# 04_Power.net
KiCad netlist of a schematic drawn in Altium Designer
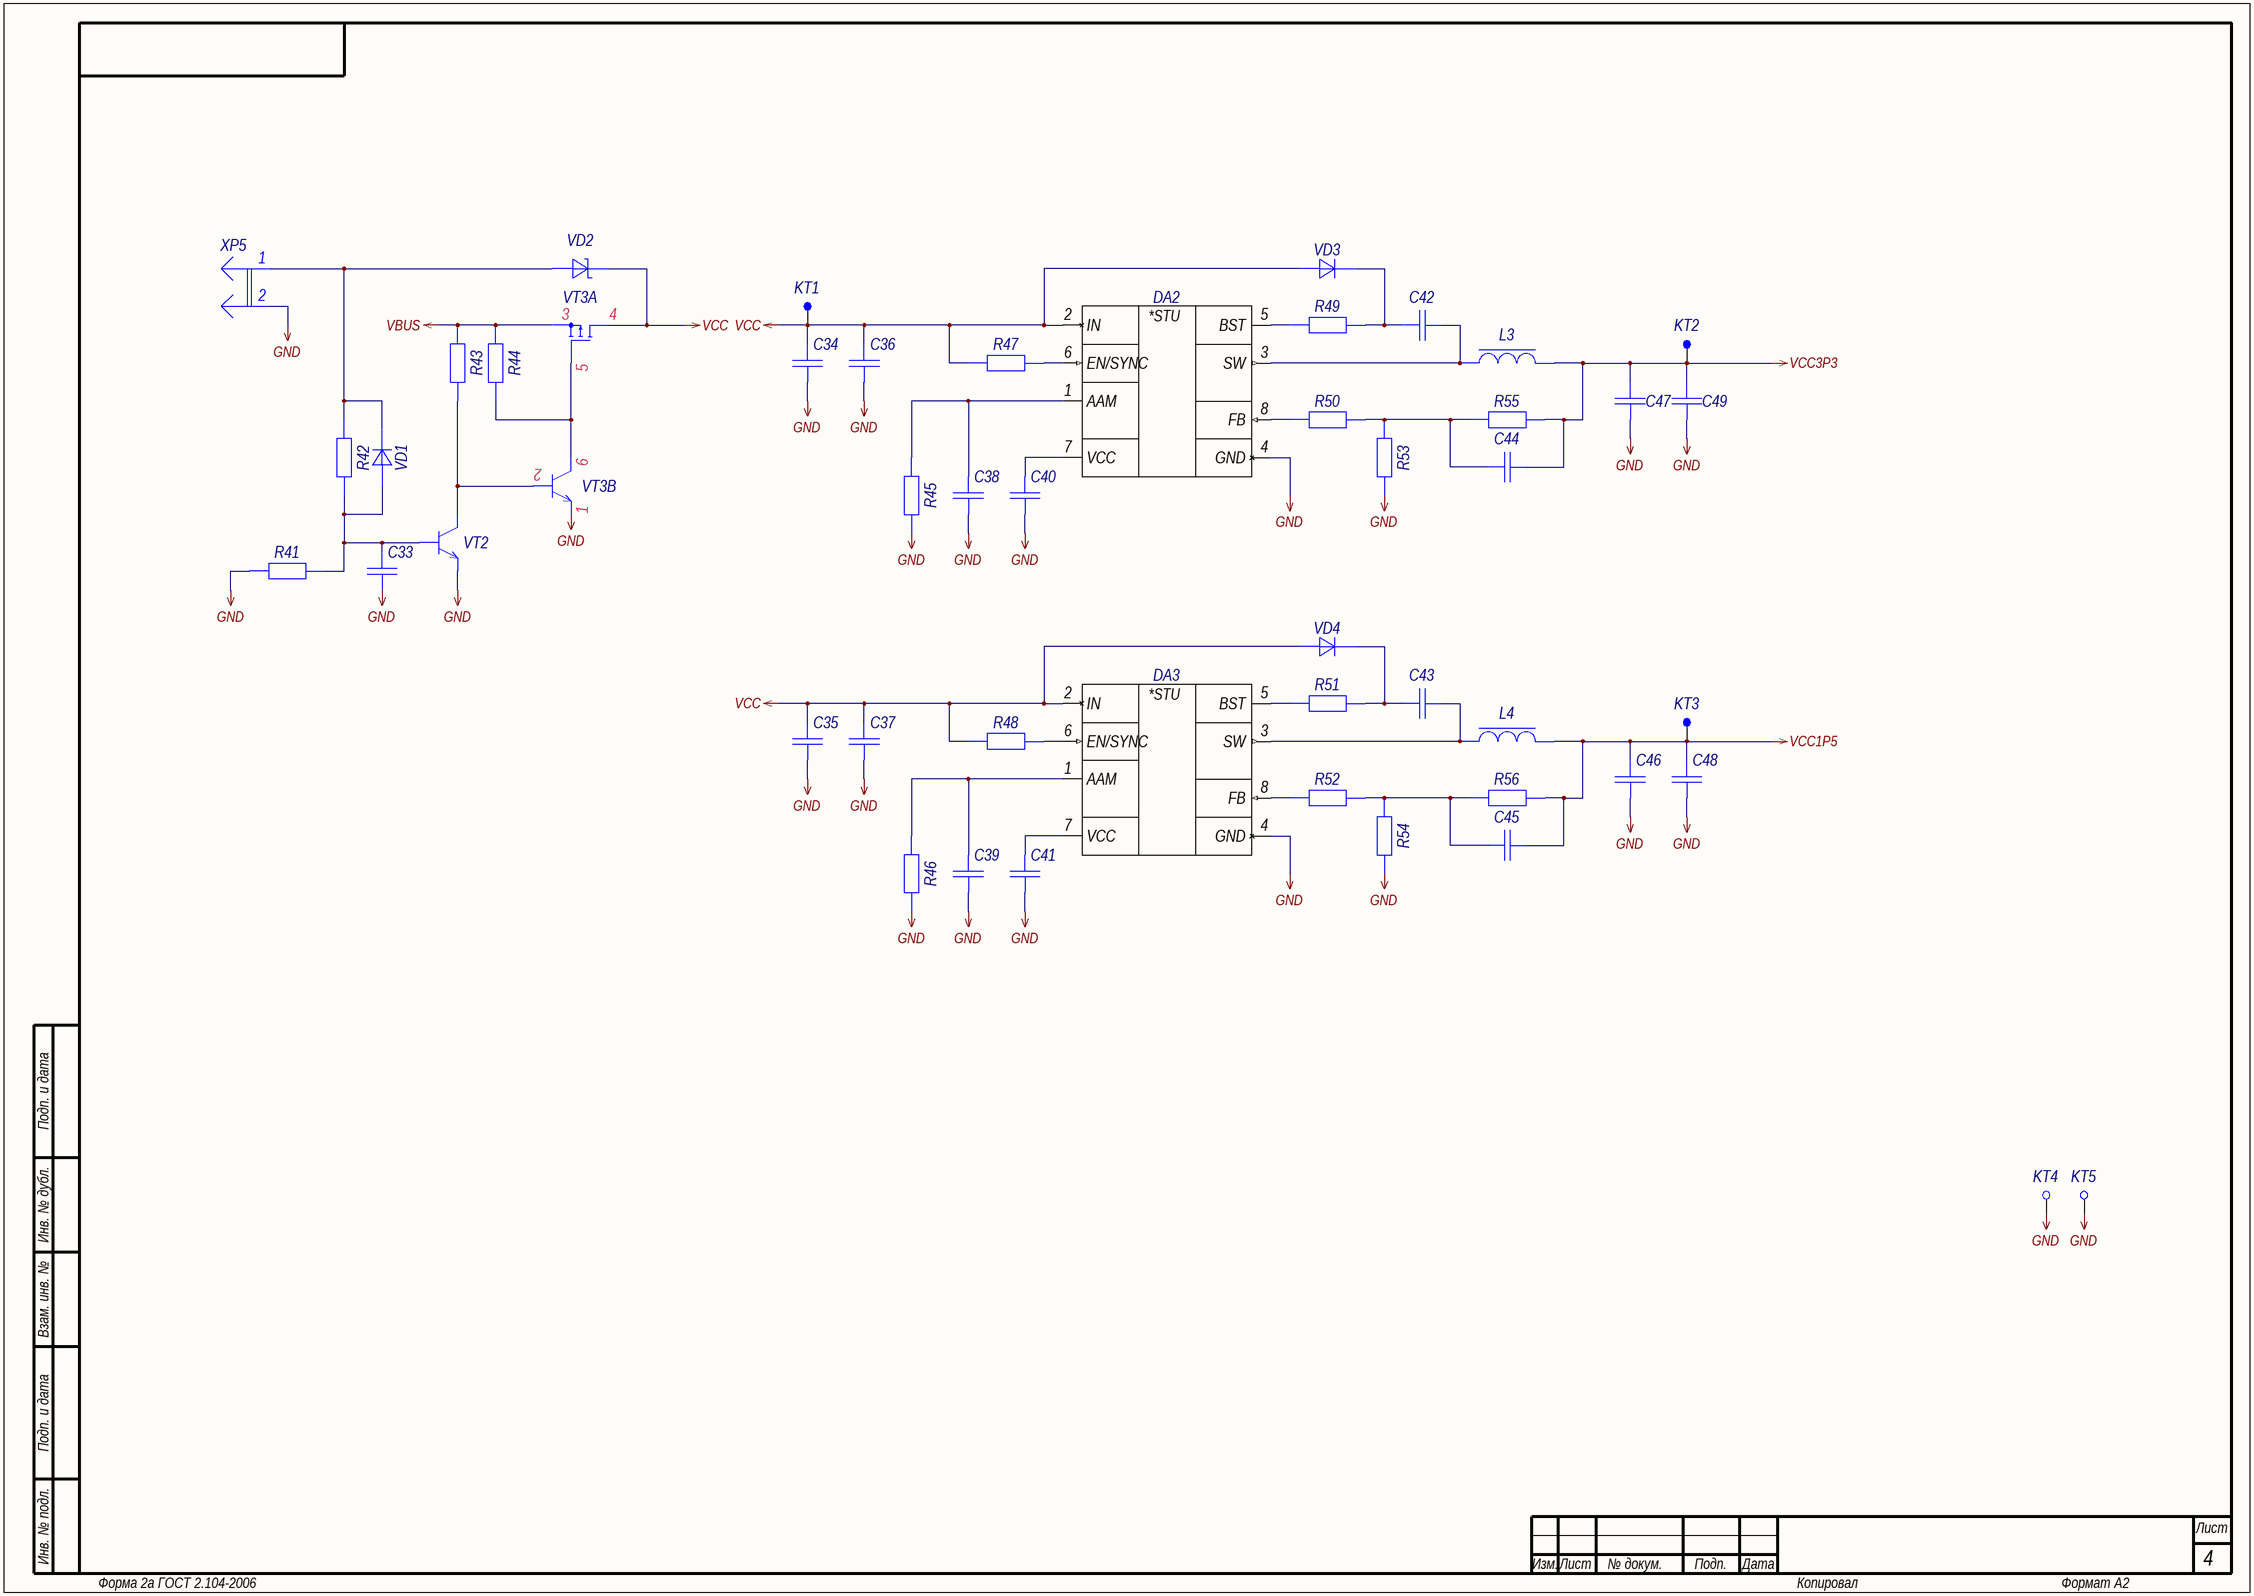
[diagram p0: 04_Power.SchDoc]

(export (version "E")
  (design (tool "Eeschema 10.0.6"))
  (components
    (comp (ref "C33")
      (value "Capacitor")
      (footprint "C0603_L")
      (fields
        (field (name "PART NUMBER") "GRM188R72A104KA35D")
        (field (name "VOLTAGE") "100V")
        (field (name "TOLERANCE") "±10%")
        (field (name "PUBLISHER") "Andrew Danich")
      )
      (libsource (lib "ADLib") (part "Capacitor"))
    )
    (comp (ref "C34")
      (value "Capacitor")
      (footprint "C1206_L")
      (fields
        (field (name "PART NUMBER") "GRM31CR71A226KE15L")
        (field (name "VOLTAGE") "10V")
        (field (name "TOLERANCE") "±10%")
        (field (name "PUBLISHER") "Andrew Danich")
      )
      (libsource (lib "ADLib") (part "Capacitor"))
    )
    (comp (ref "C35")
      (value "Capacitor")
      (footprint "C1206_L")
      (fields
        (field (name "PART NUMBER") "GRM31CR71A226KE15L")
        (field (name "VOLTAGE") "10V")
        (field (name "TOLERANCE") "±10%")
        (field (name "PUBLISHER") "Andrew Danich")
      )
      (libsource (lib "ADLib") (part "Capacitor"))
    )
    (comp (ref "C36")
      (value "Capacitor")
      (footprint "C0603_L")
      (fields
        (field (name "PART NUMBER") "GRM188R72A104KA35D")
        (field (name "VOLTAGE") "100V")
        (field (name "TOLERANCE") "±10%")
        (field (name "PUBLISHER") "Andrew Danich")
      )
      (libsource (lib "ADLib") (part "Capacitor"))
    )
    (comp (ref "C37")
      (value "Capacitor")
      (footprint "C0603_L")
      (fields
        (field (name "PART NUMBER") "GRM188R72A104KA35D")
        (field (name "VOLTAGE") "100V")
        (field (name "TOLERANCE") "±10%")
        (field (name "PUBLISHER") "Andrew Danich")
      )
      (libsource (lib "ADLib") (part "Capacitor"))
    )
    (comp (ref "C38")
      (value "Capacitor")
      (footprint "C0603_L")
      (fields
        (field (name "PART NUMBER") "GRM1885C2A102JA01D")
        (field (name "VOLTAGE") "100V")
        (field (name "TOLERANCE") "±5%")
        (field (name "PUBLISHER") "Andrew Danich")
      )
      (libsource (lib "ADLib") (part "Capacitor"))
    )
    (comp (ref "C39")
      (value "Capacitor")
      (footprint "C0603_L")
      (fields
        (field (name "PART NUMBER") "GRM1885C2A102JA01D")
        (field (name "VOLTAGE") "100V")
        (field (name "TOLERANCE") "±5%")
        (field (name "PUBLISHER") "Andrew Danich")
      )
      (libsource (lib "ADLib") (part "Capacitor"))
    )
    (comp (ref "C40")
      (value "Capacitor")
      (footprint "C0603_L")
      (fields
        (field (name "PART NUMBER") "GRM188R72A104KA35D")
        (field (name "VOLTAGE") "100V")
        (field (name "TOLERANCE") "±10%")
        (field (name "PUBLISHER") "Andrew Danich")
      )
      (libsource (lib "ADLib") (part "Capacitor"))
    )
    (comp (ref "C41")
      (value "Capacitor")
      (footprint "C0603_L")
      (fields
        (field (name "PART NUMBER") "GRM188R72A104KA35D")
        (field (name "VOLTAGE") "100V")
        (field (name "TOLERANCE") "±10%")
        (field (name "PUBLISHER") "Andrew Danich")
      )
      (libsource (lib "ADLib") (part "Capacitor"))
    )
    (comp (ref "C42")
      (value "Capacitor")
      (footprint "C0603_L")
      (fields
        (field (name "PART NUMBER") "GRM188R72A104KA35D")
        (field (name "VOLTAGE") "100V")
        (field (name "TOLERANCE") "±10%")
        (field (name "PUBLISHER") "Andrew Danich")
      )
      (libsource (lib "ADLib") (part "Capacitor"))
    )
    (comp (ref "C43")
      (value "Capacitor")
      (footprint "C0603_L")
      (fields
        (field (name "PART NUMBER") "GRM188R72A104KA35D")
        (field (name "VOLTAGE") "100V")
        (field (name "TOLERANCE") "±10%")
        (field (name "PUBLISHER") "Andrew Danich")
      )
      (libsource (lib "ADLib") (part "Capacitor"))
    )
    (comp (ref "C44")
      (value "Capacitor")
      (footprint "C0603_L")
      (fields
        (field (name "PART NUMBER") "GRM1885C1H330JA01D")
        (field (name "VOLTAGE") "50V")
        (field (name "TOLERANCE") "±5%")
        (field (name "PUBLISHER") "Andrew Danich")
      )
      (libsource (lib "ADLib") (part "Capacitor"))
    )
    (comp (ref "C45")
      (value "Capacitor")
      (footprint "C0603_L")
      (fields
        (field (name "PART NUMBER") "GRM1885C1H330JA01D")
        (field (name "VOLTAGE") "50V")
        (field (name "TOLERANCE") "±5%")
        (field (name "PUBLISHER") "Andrew Danich")
      )
      (libsource (lib "ADLib") (part "Capacitor"))
    )
    (comp (ref "C46")
      (value "Capacitor")
      (footprint "C0805_L")
      (fields
        (field (name "PART NUMBER") "GRM21BR60J226ME39L")
        (field (name "VOLTAGE") "6.3V")
        (field (name "TOLERANCE") "±20%")
        (field (name "PUBLISHER") "Andrew Danich")
      )
      (libsource (lib "ADLib") (part "Capacitor"))
    )
    (comp (ref "C47")
      (value "Capacitor")
      (footprint "C0805_L")
      (fields
        (field (name "PART NUMBER") "GRM21BR60J226ME39L")
        (field (name "VOLTAGE") "6.3V")
        (field (name "TOLERANCE") "±20%")
        (field (name "PUBLISHER") "Andrew Danich")
      )
      (libsource (lib "ADLib") (part "Capacitor"))
    )
    (comp (ref "C48")
      (value "Capacitor")
      (footprint "C0805_L")
      (fields
        (field (name "PART NUMBER") "GRM21BR60J226ME39L")
        (field (name "VOLTAGE") "6.3V")
        (field (name "TOLERANCE") "±20%")
        (field (name "PUBLISHER") "Andrew Danich")
      )
      (libsource (lib "ADLib") (part "Capacitor"))
    )
    (comp (ref "C49")
      (value "Capacitor")
      (footprint "C0805_L")
      (fields
        (field (name "PART NUMBER") "GRM21BR60J226ME39L")
        (field (name "VOLTAGE") "6.3V")
        (field (name "TOLERANCE") "±20%")
        (field (name "PUBLISHER") "Andrew Danich")
      )
      (libsource (lib "ADLib") (part "Capacitor"))
    )
    (comp (ref "DA2")
      (value "MP2315GJ")
      (footprint "TSOT-23-8_065P290X160X100_N")
      (fields
        (field (name "PART NUMBER") "MP2315GJ-Z")
        (field (name "MANUFACTURER") "Monolithic Power Systems")
        (field (name "PUBLISHER") "Andrew Danich")
      )
      (libsource (lib "ADLib") (part "MP2315GJ"))
    )
    (comp (ref "DA3")
      (value "MP2315GJ")
      (footprint "TSOT-23-8_065P290X160X100_N")
      (fields
        (field (name "PART NUMBER") "MP2315GJ-Z")
        (field (name "MANUFACTURER") "Monolithic Power Systems")
        (field (name "PUBLISHER") "Andrew Danich")
      )
      (libsource (lib "ADLib") (part "MP2315GJ"))
    )
    (comp (ref "KT1")
      (value "VCC")
      (footprint "TP-SMT-C-0.8mm")
      (fields (field (name "PART NUMBER") "TestPoint-SMT") (field (name "PUBLISHER") "Andrew Danich"))
      (libsource (lib "ADLib") (part "TP-S-1"))
    )
    (comp (ref "KT2")
      (value "+3.3В")
      (footprint "TP-SMT-C-0.8mm")
      (fields (field (name "PART NUMBER") "TestPoint-SMT") (field (name "PUBLISHER") "Andrew Danich"))
      (libsource (lib "ADLib") (part "TP-S-1"))
    )
    (comp (ref "KT3")
      (value "+1.5V")
      (footprint "TP-SMT-C-0.8mm")
      (fields (field (name "PART NUMBER") "TestPoint-SMT") (field (name "PUBLISHER") "Andrew Danich"))
      (libsource (lib "ADLib") (part "TP-S-1"))
    )
    (comp (ref "KT4")
      (value "ОБЩ")
      (footprint "5001")
      (fields
        (field (name "PART NUMBER") "5001")
        (field (name "MANUFACTURER") "Keystone Electronics")
        (field (name "PUBLISHER") "Andrew Danich")
      )
      (libsource (lib "ADLib") (part "TP-1"))
    )
    (comp (ref "KT5")
      (value "ОБЩ")
      (footprint "5001")
      (fields
        (field (name "PART NUMBER") "5001")
        (field (name "MANUFACTURER") "Keystone Electronics")
        (field (name "PUBLISHER") "Andrew Danich")
      )
      (libsource (lib "ADLib") (part "TP-1"))
    )
    (comp (ref "L3")
      (value "Coil")
      (footprint "SRP4020TA-Series")
      (fields
        (field (name "PART NUMBER") "SRP4020TA-4R7M")
        (field (name "TOLERANCE") "±20%")
        (field (name "MANUFACTURER") "Bourns")
        (field (name "PUBLISHER") "Andrew Danich")
      )
      (libsource (lib "ADLib") (part "Coil"))
    )
    (comp (ref "L4")
      (value "Coil")
      (footprint "SRP4020TA-Series")
      (fields
        (field (name "PART NUMBER") "SRP4020TA-4R7M")
        (field (name "TOLERANCE") "±20%")
        (field (name "MANUFACTURER") "Bourns")
        (field (name "PUBLISHER") "Andrew Danich")
      )
      (libsource (lib "ADLib") (part "Coil"))
    )
    (comp (ref "R41")
      (value "Resistor")
      (footprint "R0603_L")
      (fields
        (field (name "PART NUMBER") "RC0603JR-0710KL")
        (field (name "TOLERANCE") "±5%")
        (field (name "MANUFACTURER") "Yageo")
        (field (name "PUBLISHER") "Andrew Danich")
      )
      (libsource (lib "ADLib") (part "Resistor"))
    )
    (comp (ref "R42")
      (value "Resistor")
      (footprint "R0603_L")
      (fields
        (field (name "PART NUMBER") "RC0603JR-0710KL")
        (field (name "TOLERANCE") "±5%")
        (field (name "MANUFACTURER") "Yageo")
        (field (name "PUBLISHER") "Andrew Danich")
      )
      (libsource (lib "ADLib") (part "Resistor"))
    )
    (comp (ref "R43")
      (value "Resistor")
      (footprint "R0603_L")
      (fields
        (field (name "PART NUMBER") "RC0603JR-0710KL")
        (field (name "TOLERANCE") "±5%")
        (field (name "MANUFACTURER") "Yageo")
        (field (name "PUBLISHER") "Andrew Danich")
      )
      (libsource (lib "ADLib") (part "Resistor"))
    )
    (comp (ref "R44")
      (value "Resistor")
      (footprint "R0603_L")
      (fields
        (field (name "PART NUMBER") "RC0603JR-0710KL")
        (field (name "TOLERANCE") "±5%")
        (field (name "MANUFACTURER") "Yageo")
        (field (name "PUBLISHER") "Andrew Danich")
      )
      (libsource (lib "ADLib") (part "Resistor"))
    )
    (comp (ref "R45")
      (value "Resistor")
      (footprint "R0603_L")
      (fields
        (field (name "PART NUMBER") "RC0603JR-0762KL")
        (field (name "TOLERANCE") "±5%")
        (field (name "MANUFACTURER") "Yageo")
        (field (name "PUBLISHER") "Andrew Danich")
      )
      (libsource (lib "ADLib") (part "Resistor"))
    )
    (comp (ref "R46")
      (value "Resistor")
      (footprint "R0603_L")
      (fields
        (field (name "PART NUMBER") "RC0603JR-0762KL")
        (field (name "TOLERANCE") "±5%")
        (field (name "MANUFACTURER") "Yageo")
        (field (name "PUBLISHER") "Andrew Danich")
      )
      (libsource (lib "ADLib") (part "Resistor"))
    )
    (comp (ref "R47")
      (value "Resistor")
      (footprint "R0603_L")
      (fields
        (field (name "PART NUMBER") "RC0603JR-07100KL")
        (field (name "TOLERANCE") "±5%")
        (field (name "MANUFACTURER") "Yageo")
        (field (name "PUBLISHER") "Andrew Danich")
      )
      (libsource (lib "ADLib") (part "Resistor"))
    )
    (comp (ref "R48")
      (value "Resistor")
      (footprint "R0603_L")
      (fields
        (field (name "PART NUMBER") "RC0603JR-07100KL")
        (field (name "TOLERANCE") "±5%")
        (field (name "MANUFACTURER") "Yageo")
        (field (name "PUBLISHER") "Andrew Danich")
      )
      (libsource (lib "ADLib") (part "Resistor"))
    )
    (comp (ref "R49")
      (value "Resistor")
      (footprint "R0603_L")
      (fields
        (field (name "PART NUMBER") "RC0603JR-0722RL")
        (field (name "TOLERANCE") "±5%")
        (field (name "MANUFACTURER") "Yageo")
        (field (name "PUBLISHER") "Andrew Danich")
      )
      (libsource (lib "ADLib") (part "Resistor"))
    )
    (comp (ref "R50")
      (value "Resistor")
      (footprint "R0603_L")
      (fields
        (field (name "PART NUMBER") "RC0603JR-0733KL")
        (field (name "TOLERANCE") "±5%")
        (field (name "MANUFACTURER") "Yageo")
        (field (name "PUBLISHER") "Andrew Danich")
      )
      (libsource (lib "ADLib") (part "Resistor"))
    )
    (comp (ref "R51")
      (value "Resistor")
      (footprint "R0603_L")
      (fields
        (field (name "PART NUMBER") "RC0603JR-0722RL")
        (field (name "TOLERANCE") "±5%")
        (field (name "MANUFACTURER") "Yageo")
        (field (name "PUBLISHER") "Andrew Danich")
      )
      (libsource (lib "ADLib") (part "Resistor"))
    )
    (comp (ref "R52")
      (value "Resistor")
      (footprint "R0603_L")
      (fields
        (field (name "PART NUMBER") "RC0603JR-0733KL")
        (field (name "TOLERANCE") "±5%")
        (field (name "MANUFACTURER") "Yageo")
        (field (name "PUBLISHER") "Andrew Danich")
      )
      (libsource (lib "ADLib") (part "Resistor"))
    )
    (comp (ref "R53")
      (value "Resistor")
      (footprint "R0603_L")
      (fields
        (field (name "PART NUMBER") "RC0603FR-0712K7L")
        (field (name "TOLERANCE") "±1%")
        (field (name "MANUFACTURER") "Yageo")
        (field (name "PUBLISHER") "Andrew Danich")
      )
      (libsource (lib "ADLib") (part "Resistor"))
    )
    (comp (ref "R54")
      (value "Resistor")
      (footprint "R0603_L")
      (fields
        (field (name "PART NUMBER") "RC0603FR-0746K4L")
        (field (name "TOLERANCE") "±1%")
        (field (name "MANUFACTURER") "Yageo")
        (field (name "PUBLISHER") "Andrew Danich")
      )
      (libsource (lib "ADLib") (part "Resistor"))
    )
    (comp (ref "R55")
      (value "Resistor")
      (footprint "R0603_L")
      (fields
        (field (name "PART NUMBER") "RC0603FR-0740K2L")
        (field (name "TOLERANCE") "±1%")
        (field (name "MANUFACTURER") "Yageo")
        (field (name "PUBLISHER") "Andrew Danich")
      )
      (libsource (lib "ADLib") (part "Resistor"))
    )
    (comp (ref "R56")
      (value "Resistor")
      (footprint "R0603_L")
      (fields
        (field (name "PART NUMBER") "RC0603FR-0740K2L")
        (field (name "TOLERANCE") "±1%")
        (field (name "MANUFACTURER") "Yageo")
        (field (name "PUBLISHER") "Andrew Danich")
      )
      (libsource (lib "ADLib") (part "Resistor"))
    )
    (comp (ref "VD1")
      (value "Diode")
      (footprint "SOD-323")
      (fields
        (field (name "PART NUMBER") "1N4148WS-7-F")
        (field (name "MANUFACTURER") "Diodes Incorporated")
        (field (name "PUBLISHER") "Andrew Danich")
      )
      (libsource (lib "ADLib") (part "Diode"))
    )
    (comp (ref "VD2")
      (value "Schottky")
      (footprint "SOD-123")
      (fields
        (field (name "PART NUMBER") "MBR0540T1G")
        (field (name "MANUFACTURER") "ON Semiconductor")
        (field (name "PUBLISHER") "Andrew Danich")
      )
      (libsource (lib "ADLib") (part "Schottky"))
    )
    (comp (ref "VD3")
      (value "Diode")
      (footprint "SOD-323")
      (fields
        (field (name "PART NUMBER") "1N4148WS-7-F")
        (field (name "MANUFACTURER") "Diodes Incorporated")
        (field (name "PUBLISHER") "Andrew Danich")
      )
      (libsource (lib "ADLib") (part "Diode"))
    )
    (comp (ref "VD4")
      (value "Diode")
      (footprint "SOD-323")
      (fields
        (field (name "PART NUMBER") "1N4148WS-7-F")
        (field (name "MANUFACTURER") "Diodes Incorporated")
        (field (name "PUBLISHER") "Andrew Danich")
      )
      (libsource (lib "ADLib") (part "Diode"))
    )
    (comp (ref "VT2")
      (value "BJT-NPN")
      (footprint "SOT-23_190P290X160X145_N")
      (fields (field (name "PART NUMBER") "BC846") (field (name "PUBLISHER") "Andrew Danich"))
      (libsource (lib "ADLib") (part "BJT-NPN"))
    )
    (comp (ref "VT3")
      (value "PMC85XP")
      (footprint "SOT-1118-2M_065P200X200X065_N")
      (fields (field (name "MANUFACTURER") "NXP Semiconductors") (field (name "PUBLISHER") "Andrew Danich"))
      (libsource (lib "ADLib") (part "PMC85XP"))
    )
    (comp (ref "XP5")
      (value "VCC")
      (footprint "MW-2M")
      (fields (field (name "PART NUMBER") "MW-2M") (field (name "PUBLISHER") "Andrew Danich"))
      (libsource (lib "ADLib") (part "Con-2-M"))
    )
  )
  (nets
    (net (code "1") (name "GND") (class "Default")
      (node (ref "C33") (pin "1") (pinfunction "1_1") (pintype "passive"))
      (node (ref "C34") (pin "1") (pinfunction "1_1") (pintype "passive"))
      (node (ref "C35") (pin "1") (pinfunction "1_1") (pintype "passive"))
      (node (ref "C36") (pin "1") (pinfunction "1_1") (pintype "passive"))
      (node (ref "C37") (pin "1") (pinfunction "1_1") (pintype "passive"))
      (node (ref "C38") (pin "1") (pinfunction "1_1") (pintype "passive"))
      (node (ref "C39") (pin "1") (pinfunction "1_1") (pintype "passive"))
      (node (ref "C40") (pin "1") (pinfunction "1_1") (pintype "passive"))
      (node (ref "C41") (pin "1") (pinfunction "1_1") (pintype "passive"))
      (node (ref "C46") (pin "1") (pinfunction "1_1") (pintype "passive"))
      (node (ref "C47") (pin "1") (pinfunction "1_1") (pintype "passive"))
      (node (ref "C48") (pin "1") (pinfunction "1_1") (pintype "passive"))
      (node (ref "C49") (pin "1") (pinfunction "1_1") (pintype "passive"))
      (node (ref "DA2") (pin "4") (pinfunction "GND_4") (pintype "power_in"))
      (node (ref "DA3") (pin "4") (pinfunction "GND_4") (pintype "power_in"))
      (node (ref "KT4") (pin "1") (pinfunction "1_1") (pintype "passive"))
      (node (ref "KT5") (pin "1") (pinfunction "1_1") (pintype "passive"))
      (node (ref "R41") (pin "2") (pinfunction "2_2") (pintype "passive"))
      (node (ref "R45") (pin "1") (pinfunction "1_1") (pintype "passive"))
      (node (ref "R46") (pin "1") (pinfunction "1_1") (pintype "passive"))
      (node (ref "R53") (pin "1") (pinfunction "1_1") (pintype "passive"))
      (node (ref "R54") (pin "1") (pinfunction "1_1") (pintype "passive"))
      (node (ref "VT2") (pin "3") (pinfunction "Э_3") (pintype "passive"))
      (node (ref "VT3") (pin "1") (pinfunction "Э_1") (pintype "passive"))
      (node (ref "XP5") (pin "2") (pintype "passive"))
    )
    (net (code "2") (name "Net-(C44-Pad1)") (class "Default")
      (node (ref "C44") (pin "1") (pinfunction "1_1") (pintype "passive"))
      (node (ref "R50") (pin "2") (pinfunction "2_2") (pintype "passive"))
      (node (ref "R53") (pin "2") (pinfunction "2_2") (pintype "passive"))
      (node (ref "R55") (pin "1") (pinfunction "1_1") (pintype "passive"))
    )
    (net (code "3") (name "Net-(C45-Pad1)") (class "Default")
      (node (ref "C45") (pin "1") (pinfunction "1_1") (pintype "passive"))
      (node (ref "R52") (pin "2") (pinfunction "2_2") (pintype "passive"))
      (node (ref "R54") (pin "2") (pinfunction "2_2") (pintype "passive"))
      (node (ref "R56") (pin "1") (pinfunction "1_1") (pintype "passive"))
    )
    (net (code "4") (name "Net-(DA2-AAM)") (class "Default")
      (node (ref "C38") (pin "2") (pinfunction "2_2") (pintype "passive"))
      (node (ref "DA2") (pin "1") (pinfunction "AAM_1") (pintype "passive"))
      (node (ref "R45") (pin "2") (pinfunction "2_2") (pintype "passive"))
    )
    (net (code "5") (name "Net-(DA2-BST)") (class "Default")
      (node (ref "DA2") (pin "5") (pinfunction "BST_5") (pintype "passive"))
      (node (ref "R49") (pin "1") (pinfunction "1_1") (pintype "passive"))
    )
    (net (code "6") (name "Net-(DA2-EN{slash}SYNC)") (class "Default")
      (node (ref "DA2") (pin "6") (pinfunction "EN/SYNC_6") (pintype "input"))
      (node (ref "R47") (pin "2") (pinfunction "2_2") (pintype "passive"))
    )
    (net (code "7") (name "Net-(DA2-FB)") (class "Default")
      (node (ref "DA2") (pin "8") (pinfunction "FB_8") (pintype "input"))
      (node (ref "R50") (pin "1") (pinfunction "1_1") (pintype "passive"))
    )
    (net (code "8") (name "Net-(DA2-SW)") (class "Default")
      (node (ref "C42") (pin "2") (pinfunction "2_2") (pintype "passive"))
      (node (ref "DA2") (pin "3") (pinfunction "SW_3") (pintype "output"))
      (node (ref "L3") (pin "1") (pinfunction "1_1") (pintype "passive"))
    )
    (net (code "9") (name "Net-(DA2-VCC)") (class "Default")
      (node (ref "C40") (pin "2") (pinfunction "2_2") (pintype "passive"))
      (node (ref "DA2") (pin "7") (pinfunction "VCC_7") (pintype "power_in"))
    )
    (net (code "10") (name "Net-(DA3-AAM)") (class "Default")
      (node (ref "C39") (pin "2") (pinfunction "2_2") (pintype "passive"))
      (node (ref "DA3") (pin "1") (pinfunction "AAM_1") (pintype "passive"))
      (node (ref "R46") (pin "2") (pinfunction "2_2") (pintype "passive"))
    )
    (net (code "11") (name "Net-(DA3-BST)") (class "Default")
      (node (ref "DA3") (pin "5") (pinfunction "BST_5") (pintype "passive"))
      (node (ref "R51") (pin "1") (pinfunction "1_1") (pintype "passive"))
    )
    (net (code "12") (name "Net-(DA3-EN{slash}SYNC)") (class "Default")
      (node (ref "DA3") (pin "6") (pinfunction "EN/SYNC_6") (pintype "input"))
      (node (ref "R48") (pin "2") (pinfunction "2_2") (pintype "passive"))
    )
    (net (code "13") (name "Net-(DA3-FB)") (class "Default")
      (node (ref "DA3") (pin "8") (pinfunction "FB_8") (pintype "input"))
      (node (ref "R52") (pin "1") (pinfunction "1_1") (pintype "passive"))
    )
    (net (code "14") (name "Net-(DA3-SW)") (class "Default")
      (node (ref "C43") (pin "2") (pinfunction "2_2") (pintype "passive"))
      (node (ref "DA3") (pin "3") (pinfunction "SW_3") (pintype "output"))
      (node (ref "L4") (pin "1") (pinfunction "1_1") (pintype "passive"))
    )
    (net (code "15") (name "Net-(DA3-VCC)") (class "Default")
      (node (ref "C41") (pin "2") (pinfunction "2_2") (pintype "passive"))
      (node (ref "DA3") (pin "7") (pinfunction "VCC_7") (pintype "power_in"))
    )
    (net (code "16") (name "Net-(VD1-А)") (class "Default")
      (node (ref "C33") (pin "2") (pinfunction "2_2") (pintype "passive"))
      (node (ref "R41") (pin "1") (pinfunction "1_1") (pintype "passive"))
      (node (ref "R42") (pin "1") (pinfunction "1_1") (pintype "passive"))
      (node (ref "VD1") (pin "1") (pinfunction "А_1") (pintype "passive"))
      (node (ref "VT2") (pin "1") (pinfunction "Б_1") (pintype "passive"))
    )
    (net (code "17") (name "Net-(VD1-К)") (class "Default")
      (node (ref "R42") (pin "2") (pinfunction "2_2") (pintype "passive"))
      (node (ref "VD1") (pin "2") (pinfunction "К_2") (pintype "passive"))
      (node (ref "VD2") (pin "1") (pinfunction "А_1") (pintype "passive"))
      (node (ref "XP5") (pin "1") (pintype "passive"))
    )
    (net (code "18") (name "Net-(VD3-К)") (class "Default")
      (node (ref "C42") (pin "1") (pinfunction "1_1") (pintype "passive"))
      (node (ref "R49") (pin "2") (pinfunction "2_2") (pintype "passive"))
      (node (ref "VD3") (pin "2") (pinfunction "К_2") (pintype "passive"))
    )
    (net (code "19") (name "Net-(VD4-К)") (class "Default")
      (node (ref "C43") (pin "1") (pinfunction "1_1") (pintype "passive"))
      (node (ref "R51") (pin "2") (pinfunction "2_2") (pintype "passive"))
      (node (ref "VD4") (pin "2") (pinfunction "К_2") (pintype "passive"))
    )
    (net (code "20") (name "Net-(VT2-К)") (class "Default")
      (node (ref "R43") (pin "1") (pinfunction "1_1") (pintype "passive"))
      (node (ref "VT2") (pin "2") (pinfunction "К_2") (pintype "passive"))
      (node (ref "VT3") (pin "2") (pinfunction "Б_2") (pintype "passive"))
    )
    (net (code "21") (name "Net-(VT3A-G)") (class "Default")
      (node (ref "R44") (pin "1") (pinfunction "1_1") (pintype "passive"))
      (node (ref "VT3") (pin "5") (pinfunction "G_5") (pintype "passive"))
      (node (ref "VT3") (pin "6") (pinfunction "К_6") (pintype "passive"))
    )
    (net (code "22") (name "VBUS") (class "Default")
      (node (ref "R43") (pin "2") (pinfunction "2_2") (pintype "passive"))
      (node (ref "R44") (pin "2") (pinfunction "2_2") (pintype "passive"))
      (node (ref "VT3") (pin "3") (pinfunction "S_3") (pintype "passive"))
    )
    (net (code "23") (name "VCC") (class "Default")
      (node (ref "C34") (pin "2") (pinfunction "2_2") (pintype "passive"))
      (node (ref "C35") (pin "2") (pinfunction "2_2") (pintype "passive"))
      (node (ref "C36") (pin "2") (pinfunction "2_2") (pintype "passive"))
      (node (ref "C37") (pin "2") (pinfunction "2_2") (pintype "passive"))
      (node (ref "DA2") (pin "2") (pinfunction "IN_2") (pintype "power_in"))
      (node (ref "DA3") (pin "2") (pinfunction "IN_2") (pintype "power_in"))
      (node (ref "KT1") (pin "1") (pinfunction "1_1") (pintype "passive"))
      (node (ref "R47") (pin "1") (pinfunction "1_1") (pintype "passive"))
      (node (ref "R48") (pin "1") (pinfunction "1_1") (pintype "passive"))
      (node (ref "VD2") (pin "2") (pinfunction "К_2") (pintype "passive"))
      (node (ref "VD3") (pin "1") (pinfunction "А_1") (pintype "passive"))
      (node (ref "VD4") (pin "1") (pinfunction "А_1") (pintype "passive"))
      (node (ref "VT3") (pin "4") (pinfunction "D_4") (pintype "passive"))
    )
    (net (code "24") (name "VCC1P5") (class "Default")
      (node (ref "C45") (pin "2") (pinfunction "2_2") (pintype "passive"))
      (node (ref "C46") (pin "2") (pinfunction "2_2") (pintype "passive"))
      (node (ref "C48") (pin "2") (pinfunction "2_2") (pintype "passive"))
      (node (ref "KT3") (pin "1") (pinfunction "1_1") (pintype "passive"))
      (node (ref "L4") (pin "2") (pinfunction "2_2") (pintype "passive"))
      (node (ref "R56") (pin "2") (pinfunction "2_2") (pintype "passive"))
    )
    (net (code "25") (name "VCC3P3") (class "Default")
      (node (ref "C44") (pin "2") (pinfunction "2_2") (pintype "passive"))
      (node (ref "C47") (pin "2") (pinfunction "2_2") (pintype "passive"))
      (node (ref "C49") (pin "2") (pinfunction "2_2") (pintype "passive"))
      (node (ref "KT2") (pin "1") (pinfunction "1_1") (pintype "passive"))
      (node (ref "L3") (pin "2") (pinfunction "2_2") (pintype "passive"))
      (node (ref "R55") (pin "2") (pinfunction "2_2") (pintype "passive"))
    )
  )
)
